# turtlebot.net
KiCad netlist of a schematic drawn in EAGLE
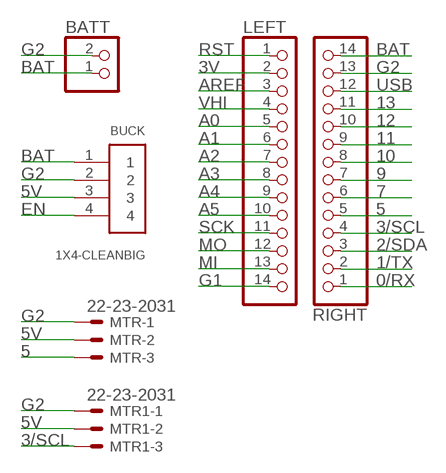
[diagram p0: schematic, sheet 1]

(export (version "E")
  (design (tool "Eeschema 10.0.6"))
  (components
    (comp (ref "BATT")
      (value "JST_2PIN-THM-RA")
      (footprint "eagle-import:JST-PH-2-THM-RA")
      (libsource (lib "eagle-import") (part "JST_2PIN-THM-RA"))
    )
    (comp (ref "BUCK")
      (value "1X4-CLEANBIG")
      (footprint "eagle-import:1X04-CLEANBIG")
      (libsource (lib "eagle-import") (part "1X4-CLEANBIG"))
    )
    (comp (ref "LEFT")
      (value "MICROBUILDER_HEADER-1X14")
      (footprint "eagle-import:MICROBUILDER_1X14_ROUND70")
      (libsource (lib "eagle-import") (part "MICROBUILDER_HEADER-1X14"))
    )
    (comp (ref "MTR")
      (value "22-23-2031")
      (footprint "eagle-import:22-23-2031")
      (fields (field (name "MF") "MOLEX"))
      (libsource (lib "eagle-import") (part "22-23-2031"))
    )
    (comp (ref "MTR1")
      (value "22-23-2031")
      (footprint "eagle-import:22-23-2031")
      (fields (field (name "MF") "MOLEX"))
      (libsource (lib "eagle-import") (part "22-23-2031"))
    )
    (comp (ref "RIGHT")
      (value "MICROBUILDER_HEADER-1X14")
      (footprint "eagle-import:MICROBUILDER_1X14_ROUND70")
      (libsource (lib "eagle-import") (part "MICROBUILDER_HEADER-1X14"))
    )
  )
  (nets
    (net (code "1") (name "/0{slash}RX") (class "Default")
      (node (ref "RIGHT") (pin "1") (pinfunction "1_1") (pintype "passive"))
    )
    (net (code "2") (name "/1{slash}TX") (class "Default")
      (node (ref "RIGHT") (pin "2") (pinfunction "2_2") (pintype "passive"))
    )
    (net (code "3") (name "/2{slash}SDA") (class "Default")
      (node (ref "RIGHT") (pin "3") (pinfunction "3_3") (pintype "passive"))
    )
    (net (code "4") (name "/3V") (class "Default")
      (node (ref "LEFT") (pin "2") (pinfunction "2_2") (pintype "passive"))
    )
    (net (code "5") (name "/3{slash}SCL") (class "Default")
      (node (ref "MTR1") (pin "3") (pinfunction "S_3") (pintype "passive"))
      (node (ref "RIGHT") (pin "4") (pinfunction "4_4") (pintype "passive"))
    )
    (net (code "6") (name "/5") (class "Default")
      (node (ref "MTR") (pin "3") (pinfunction "S_3") (pintype "passive"))
      (node (ref "RIGHT") (pin "5") (pinfunction "5_5") (pintype "passive"))
    )
    (net (code "7") (name "/5V") (class "Default")
      (node (ref "BUCK") (pin "3") (pinfunction "3_3") (pintype "bidirectional"))
      (node (ref "MTR") (pin "2") (pinfunction "S_2") (pintype "passive"))
      (node (ref "MTR1") (pin "2") (pinfunction "S_2") (pintype "passive"))
    )
    (net (code "8") (name "/7") (class "Default")
      (node (ref "RIGHT") (pin "6") (pinfunction "6_6") (pintype "passive"))
    )
    (net (code "9") (name "/9") (class "Default")
      (node (ref "RIGHT") (pin "7") (pinfunction "7_7") (pintype "passive"))
    )
    (net (code "10") (name "/10") (class "Default")
      (node (ref "RIGHT") (pin "8") (pinfunction "8_8") (pintype "passive"))
    )
    (net (code "11") (name "/11") (class "Default")
      (node (ref "RIGHT") (pin "9") (pinfunction "9_9") (pintype "passive"))
    )
    (net (code "12") (name "/12") (class "Default")
      (node (ref "RIGHT") (pin "10") (pinfunction "10_10") (pintype "passive"))
    )
    (net (code "13") (name "/13") (class "Default")
      (node (ref "RIGHT") (pin "11") (pinfunction "11_11") (pintype "passive"))
    )
    (net (code "14") (name "/A0") (class "Default")
      (node (ref "LEFT") (pin "5") (pinfunction "5_5") (pintype "passive"))
    )
    (net (code "15") (name "/A1") (class "Default")
      (node (ref "LEFT") (pin "6") (pinfunction "6_6") (pintype "passive"))
    )
    (net (code "16") (name "/A2") (class "Default")
      (node (ref "LEFT") (pin "7") (pinfunction "7_7") (pintype "passive"))
    )
    (net (code "17") (name "/A3") (class "Default")
      (node (ref "LEFT") (pin "8") (pinfunction "8_8") (pintype "passive"))
    )
    (net (code "18") (name "/A4") (class "Default")
      (node (ref "LEFT") (pin "9") (pinfunction "9_9") (pintype "passive"))
    )
    (net (code "19") (name "/A5") (class "Default")
      (node (ref "LEFT") (pin "10") (pinfunction "10_10") (pintype "passive"))
    )
    (net (code "20") (name "/AREF") (class "Default")
      (node (ref "LEFT") (pin "3") (pinfunction "3_3") (pintype "passive"))
    )
    (net (code "21") (name "/BAT") (class "Default")
      (node (ref "BATT") (pin "1") (pinfunction "2_1") (pintype "passive"))
      (node (ref "BUCK") (pin "1") (pinfunction "1_1") (pintype "bidirectional"))
      (node (ref "RIGHT") (pin "14") (pinfunction "14_14") (pintype "passive"))
    )
    (net (code "22") (name "/EN") (class "Default")
      (node (ref "BUCK") (pin "4") (pinfunction "4_4") (pintype "bidirectional"))
    )
    (net (code "23") (name "/G1") (class "Default")
      (node (ref "LEFT") (pin "14") (pinfunction "14_14") (pintype "passive"))
    )
    (net (code "24") (name "/G2") (class "Default")
      (node (ref "BATT") (pin "2") (pinfunction "1_2") (pintype "passive"))
      (node (ref "BUCK") (pin "2") (pinfunction "2_2") (pintype "bidirectional"))
      (node (ref "MTR") (pin "1") (pinfunction "S_1") (pintype "passive"))
      (node (ref "MTR1") (pin "1") (pinfunction "S_1") (pintype "passive"))
      (node (ref "RIGHT") (pin "13") (pinfunction "13_13") (pintype "passive"))
    )
    (net (code "25") (name "/MI") (class "Default")
      (node (ref "LEFT") (pin "13") (pinfunction "13_13") (pintype "passive"))
    )
    (net (code "26") (name "/MO") (class "Default")
      (node (ref "LEFT") (pin "12") (pinfunction "12_12") (pintype "passive"))
    )
    (net (code "27") (name "/RST") (class "Default")
      (node (ref "LEFT") (pin "1") (pinfunction "1_1") (pintype "passive"))
    )
    (net (code "28") (name "/SCK") (class "Default")
      (node (ref "LEFT") (pin "11") (pinfunction "11_11") (pintype "passive"))
    )
    (net (code "29") (name "/USB") (class "Default")
      (node (ref "RIGHT") (pin "12") (pinfunction "12_12") (pintype "passive"))
    )
    (net (code "30") (name "/VHI") (class "Default")
      (node (ref "LEFT") (pin "4") (pinfunction "4_4") (pintype "passive"))
    )
  )
)
